# USBToSerial.net
KiCad netlist of a schematic drawn in Altium Designer
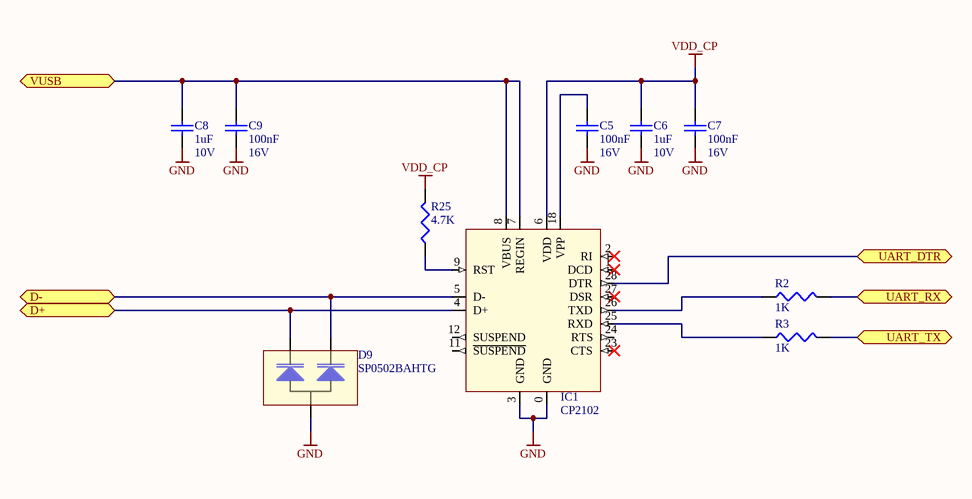
[diagram p0: USBToSerial.SchDoc]

(export (version "E")
  (design (tool "Eeschema 10.0.6"))
  (components
    (comp (ref "C5")
      (value "100nF")
      (footprint "C0603")
      (description "Capacitor, 100nF, 16V, X7R")
      (fields (field (name "VOLTAGE RATING") "16V"))
      (libsource (lib "AR_Capacitors_Ceramic") (part "100nF/0603/CER/16V"))
    )
    (comp (ref "C6")
      (value "1uF")
      (footprint "C0603")
      (description "Capacitor, 1uF, 10V, X5R")
      (fields (field (name "VOLTAGE RATING") "10V"))
      (libsource (lib "AR_Capacitors_Ceramic") (part "1uF/0603/CER/10V/X5R"))
    )
    (comp (ref "C7")
      (value "100nF")
      (footprint "C0603")
      (description "Capacitor, 100nF, 16V, X7R")
      (fields (field (name "VOLTAGE RATING") "16V"))
      (libsource (lib "AR_Capacitors_Ceramic") (part "100nF/0603/CER/16V"))
    )
    (comp (ref "C8")
      (value "1uF")
      (footprint "C0603")
      (description "Capacitor, 1uF, 10V, X5R")
      (fields (field (name "VOLTAGE RATING") "10V"))
      (libsource (lib "AR_Capacitors_Ceramic") (part "1uF/0603/CER/10V/X5R"))
    )
    (comp (ref "C9")
      (value "100nF")
      (footprint "C0603")
      (description "Capacitor, 100nF, 16V, X7R")
      (fields (field (name "VOLTAGE RATING") "16V"))
      (libsource (lib "AR_Capacitors_Ceramic") (part "100nF/0603/CER/16V"))
    )
    (comp (ref "D9")
      (value "SP0502BAHTG")
      (footprint "SOT23")
      (description "Diode TVS Dual, Vrwm: 5.5V Vc: 8V")
      (libsource (lib "AR_Diodes") (part "SP0502BAHTG"))
    )
    (comp (ref "IC1")
      (value "CP2102")
      (footprint "QFN28")
      (description "USB to UART converter")
      (libsource (lib "DannyLib") (part "CP2102"))
    )
    (comp (ref "R2")
      (value "1K")
      (footprint "0603")
      (description "Resistor, 1K, 1%, 0.063W, 50V, 100PPM, 0603")
      (libsource (lib "AR_Resistors_SMD") (part "1K/0603/0063W/50V"))
    )
    (comp (ref "R3")
      (value "1K")
      (footprint "0603")
      (description "Resistor, 1K, 1%, 0.063W, 50V, 100PPM, 0603")
      (libsource (lib "AR_Resistors_SMD") (part "1K/0603/0063W/50V"))
    )
    (comp (ref "R25")
      (value "4.7K")
      (footprint "0603")
      (description "Resistor, 4.7K, 1%, 0.063W, 60V, 100PPM, 0603")
      (libsource (lib "AR_Resistors_SMD") (part "4.7K/0603/0063W/50V"))
    )
  )
  (nets
    (net (code "1") (name "/D+") (class "Default")
      (node (ref "D9") (pin "K2") (pinfunction "K2_K2") (pintype "passive"))
      (node (ref "IC1") (pin "4") (pinfunction "D+_4") (pintype "bidirectional"))
    )
    (net (code "2") (name "/D-") (class "Default")
      (node (ref "D9") (pin "K1") (pinfunction "K1_K1") (pintype "passive"))
      (node (ref "IC1") (pin "5") (pinfunction "D-_5") (pintype "bidirectional"))
    )
    (net (code "3") (name "/UART_DTR") (class "Default")
      (node (ref "IC1") (pin "28") (pinfunction "DTR_28") (pintype "output"))
    )
    (net (code "4") (name "/UART_RX") (class "Default")
      (node (ref "R2") (pin "2") (pinfunction "2_2") (pintype "passive"))
    )
    (net (code "5") (name "/UART_TX") (class "Default")
      (node (ref "R3") (pin "2") (pinfunction "2_2") (pintype "passive"))
    )
    (net (code "6") (name "/VUSB") (class "Default")
      (node (ref "C8") (pin "2") (pinfunction "2_2") (pintype "passive"))
      (node (ref "C9") (pin "2") (pinfunction "2_2") (pintype "passive"))
      (node (ref "IC1") (pin "7") (pinfunction "REGIN_7") (pintype "power_in"))
      (node (ref "IC1") (pin "8") (pinfunction "VBUS_8") (pintype "power_in"))
    )
    (net (code "7") (name "GND") (class "Default")
      (node (ref "C5") (pin "1") (pinfunction "1_1") (pintype "passive"))
      (node (ref "C6") (pin "1") (pinfunction "1_1") (pintype "passive"))
      (node (ref "C7") (pin "1") (pinfunction "1_1") (pintype "passive"))
      (node (ref "C8") (pin "1") (pinfunction "1_1") (pintype "passive"))
      (node (ref "C9") (pin "1") (pinfunction "1_1") (pintype "passive"))
      (node (ref "D9") (pin "A") (pinfunction "A_A") (pintype "passive"))
      (node (ref "IC1") (pin "0") (pinfunction "GND_0") (pintype "power_in"))
      (node (ref "IC1") (pin "3") (pinfunction "GND_3") (pintype "power_in"))
    )
    (net (code "8") (name "Net-(IC1-RST)") (class "Default")
      (node (ref "IC1") (pin "9") (pinfunction "RST_9") (pintype "input"))
      (node (ref "R25") (pin "1") (pinfunction "1_1") (pintype "passive"))
    )
    (net (code "9") (name "Net-(IC1-RXD)") (class "Default")
      (node (ref "IC1") (pin "25") (pinfunction "RXD_25") (pintype "input"))
      (node (ref "R3") (pin "1") (pinfunction "1_1") (pintype "passive"))
    )
    (net (code "10") (name "Net-(IC1-TXD)") (class "Default")
      (node (ref "IC1") (pin "26") (pinfunction "TXD_26") (pintype "output"))
      (node (ref "R2") (pin "1") (pinfunction "1_1") (pintype "passive"))
    )
    (net (code "11") (name "Net-(IC1-VPP)") (class "Default")
      (node (ref "C5") (pin "2") (pinfunction "2_2") (pintype "passive"))
      (node (ref "IC1") (pin "18") (pinfunction "VPP_18") (pintype "power_in"))
    )
    (net (code "12") (name "VDD_CP") (class "Default")
      (node (ref "C6") (pin "2") (pinfunction "2_2") (pintype "passive"))
      (node (ref "C7") (pin "2") (pinfunction "2_2") (pintype "passive"))
      (node (ref "IC1") (pin "6") (pinfunction "VDD_6") (pintype "power_in"))
      (node (ref "R25") (pin "2") (pinfunction "2_2") (pintype "passive"))
    )
    (net (code "13") (name "unconnected-(IC1-CTS-Pad23)") (class "Default")
      (node (ref "IC1") (pin "23") (pinfunction "CTS_23") (pintype "input+no_connect"))
    )
    (net (code "14") (name "unconnected-(IC1-DCD-Pad1)") (class "Default")
      (node (ref "IC1") (pin "1") (pinfunction "DCD_1") (pintype "input+no_connect"))
    )
    (net (code "15") (name "unconnected-(IC1-DSR-Pad27)") (class "Default")
      (node (ref "IC1") (pin "27") (pinfunction "DSR_27") (pintype "input+no_connect"))
    )
    (net (code "16") (name "unconnected-(IC1-RI-Pad2)") (class "Default")
      (node (ref "IC1") (pin "2") (pinfunction "RI_2") (pintype "input+no_connect"))
    )
    (net (code "17") (name "unconnected-(IC1-RTS-Pad24)") (class "Default")
      (node (ref "IC1") (pin "24") (pinfunction "RTS_24") (pintype "output"))
    )
    (net (code "18") (name "unconnected-(IC1-SUSPEND-Pad12)") (class "Default")
      (node (ref "IC1") (pin "12") (pinfunction "SUSPEND_12") (pintype "output"))
    )
    (net (code "19") (name "unconnected-(IC1-~{SUSPEND}-Pad11)") (class "Default")
      (node (ref "IC1") (pin "11") (pinfunction "~{SUSPEND}_11") (pintype "output"))
    )
  )
)
